# datalogger-v12.net
KiCad netlist of a schematic drawn in EAGLE
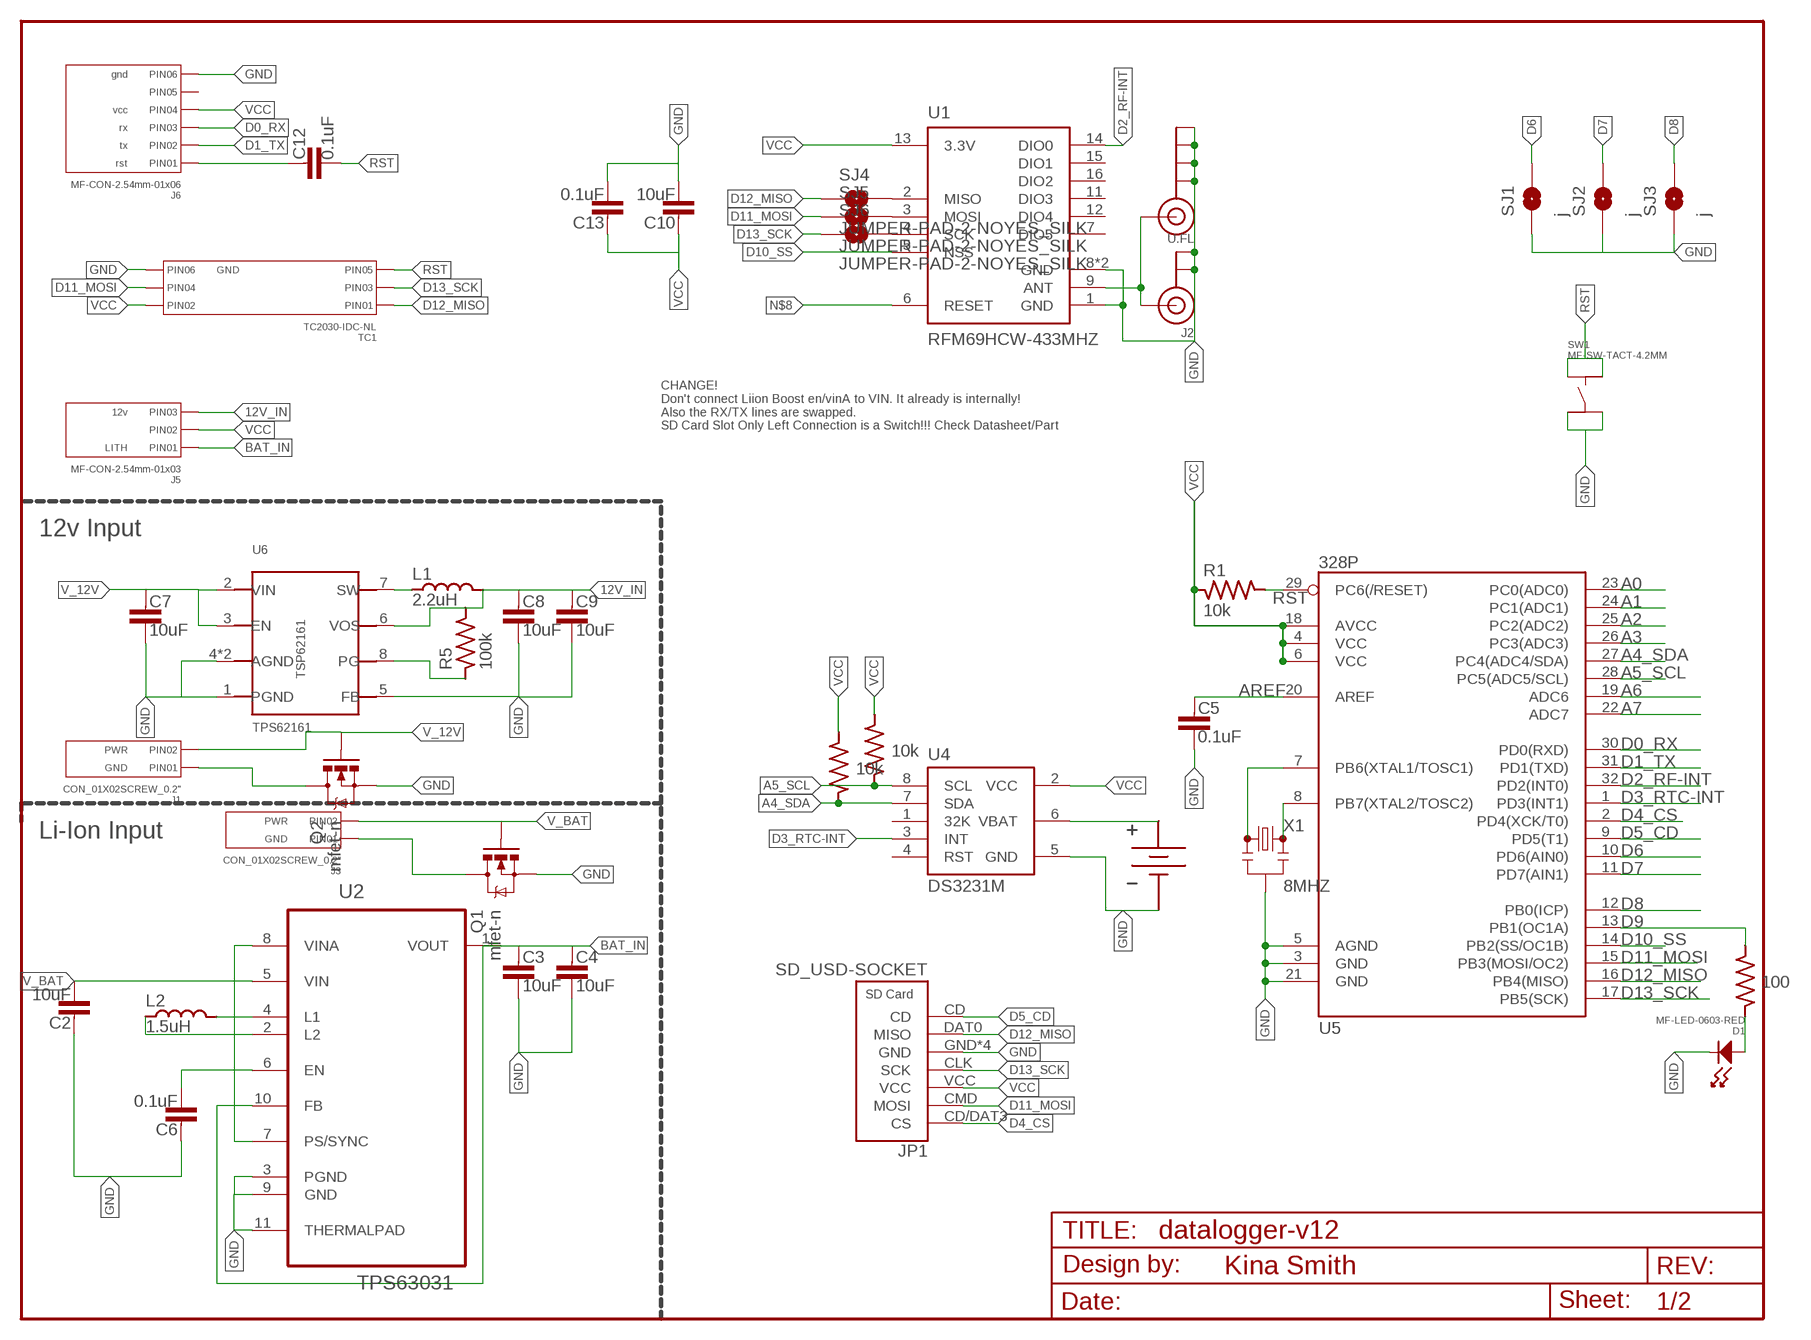
[diagram p0: schematic, sheet 1]
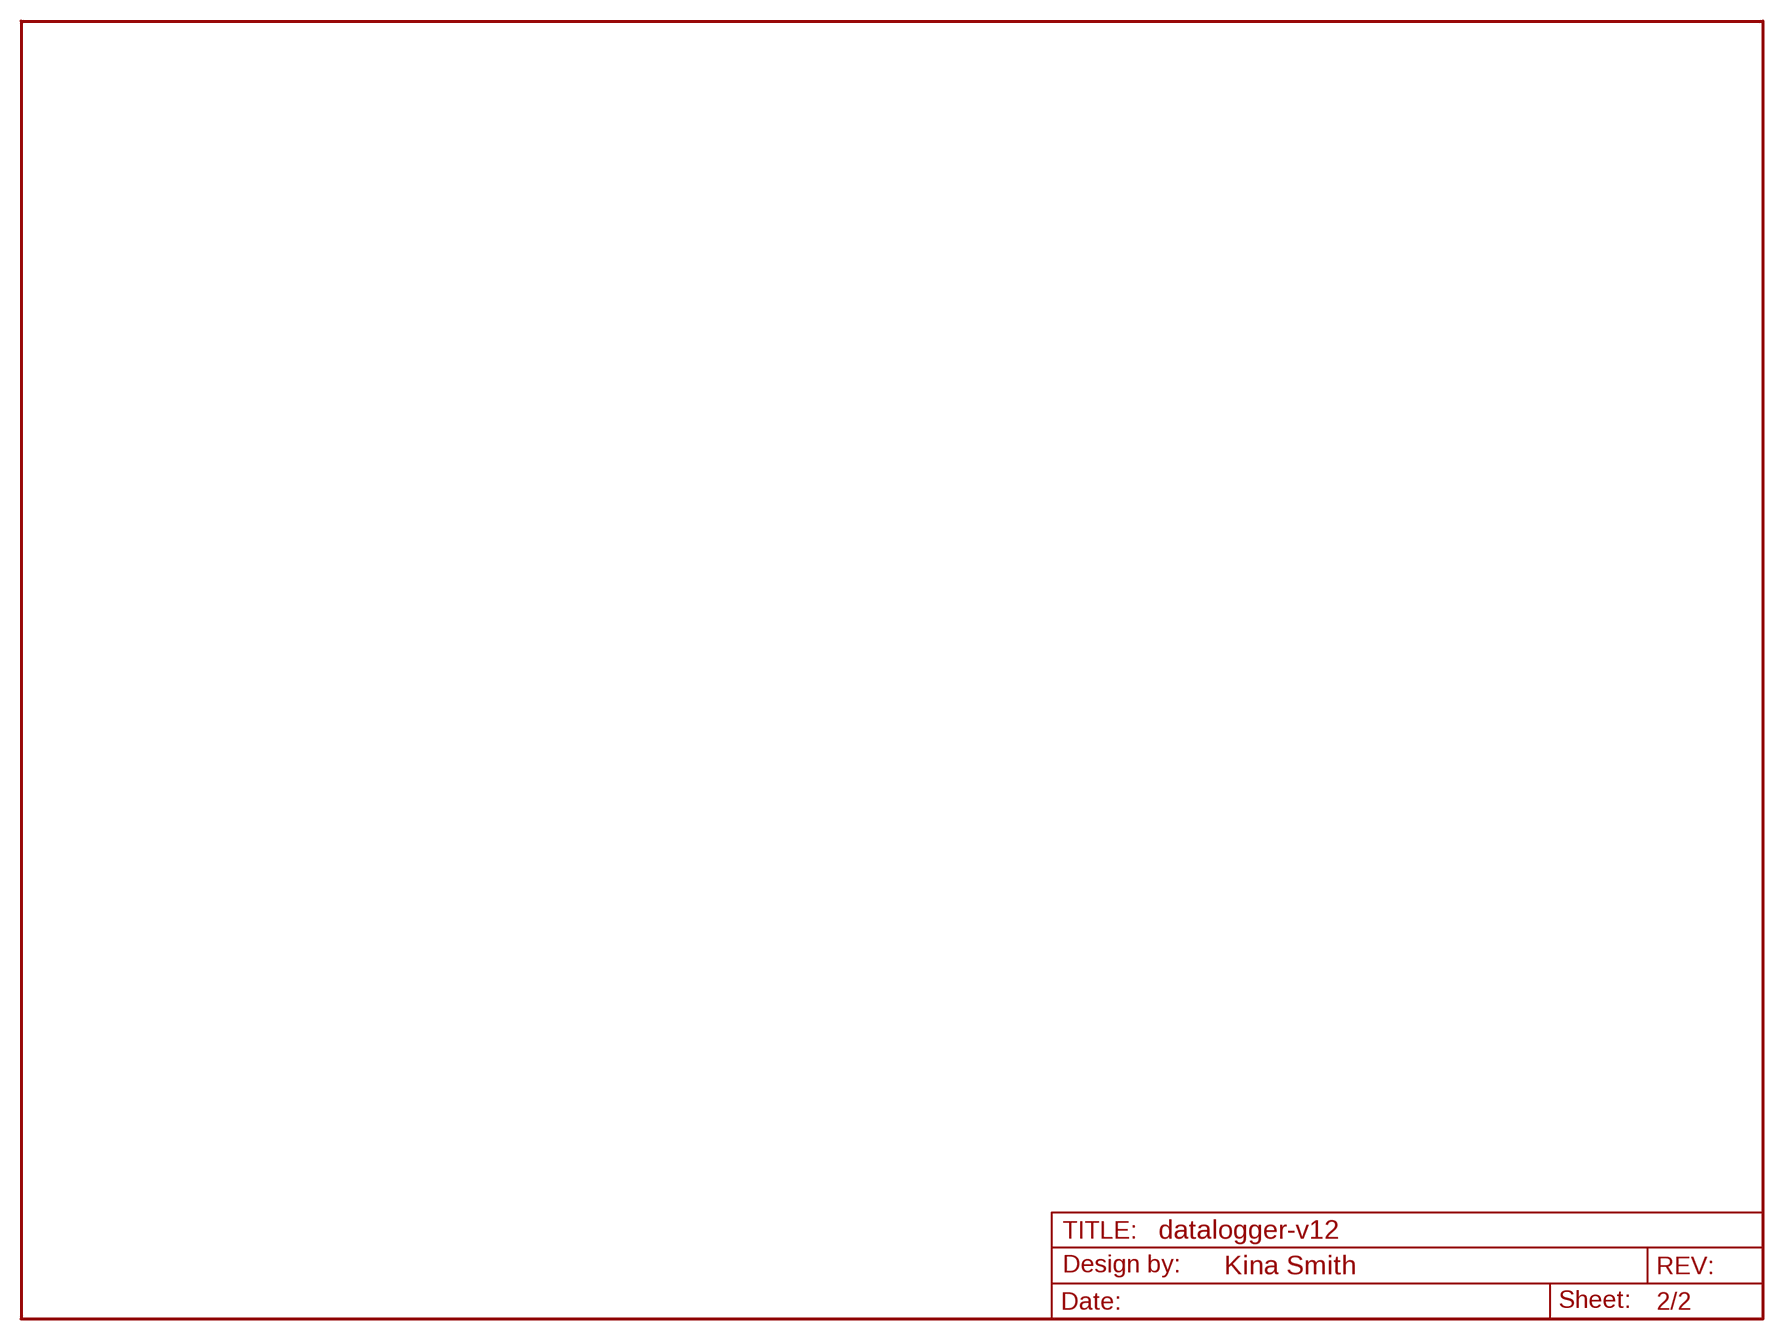
[diagram p1: schematic, sheet 2]

(export (version "E")
  (design (tool "Eeschema 10.0.6"))
  (components
    (comp (ref "BAT1")
      (value "BATTERY_HOLDER12MM")
      (footprint "eagle-import:BAT_12MM")
      (fields (field (name "PARTNO") "BK-885-TR"))
      (libsource (lib "eagle-import") (part "BATTERY_HOLDER12MM"))
    )
    (comp (ref "C2")
      (value "10uF")
      (footprint "eagle-import:C0805-N")
      (fields (field (name "PARTNO") "GRM21BR61C106KE15L"))
      (libsource (lib "eagle-import") (part "CAPACITOR_NP0805-N"))
    )
    (comp (ref "C3")
      (value "10uF")
      (footprint "eagle-import:C0805-N")
      (fields (field (name "PARTNO") "GRM21BR61C106KE15L"))
      (libsource (lib "eagle-import") (part "CAPACITOR_NP0805-N"))
    )
    (comp (ref "C4")
      (value "10uF")
      (footprint "eagle-import:C0805-N")
      (fields (field (name "PARTNO") "GRM21BR61C106KE15L"))
      (libsource (lib "eagle-import") (part "CAPACITOR_NP0805-N"))
    )
    (comp (ref "C5")
      (value "0.1uF")
      (footprint "eagle-import:C0603-N")
      (fields (field (name "PARTNO") "CC0603KRX7R7BB104"))
      (libsource (lib "eagle-import") (part "CAPACITOR_NP0603-N"))
    )
    (comp (ref "C6")
      (value "0.1uF")
      (footprint "eagle-import:C0603-N")
      (fields (field (name "PARTNO") "CC0603KRX7R7BB104"))
      (libsource (lib "eagle-import") (part "CAPACITOR_NP0603-N"))
    )
    (comp (ref "C7")
      (value "10uF")
      (footprint "eagle-import:C0805-N")
      (fields (field (name "PARTNO") "GRM21BR61C106KE15L"))
      (libsource (lib "eagle-import") (part "CAPACITOR_NP0805-N"))
    )
    (comp (ref "C8")
      (value "10uF")
      (footprint "eagle-import:C0805-N")
      (fields (field (name "PARTNO") "GRM21BR61C106KE15L"))
      (libsource (lib "eagle-import") (part "CAPACITOR_NP0805-N"))
    )
    (comp (ref "C9")
      (value "10uF")
      (footprint "eagle-import:C0805-N")
      (fields (field (name "PARTNO") "GRM21BR61C106KE15L"))
      (libsource (lib "eagle-import") (part "CAPACITOR_NP0805-N"))
    )
    (comp (ref "C10")
      (value "10uF")
      (footprint "eagle-import:C0805-N")
      (fields (field (name "PARTNO") "GRM21BR61C106KE15L"))
      (libsource (lib "eagle-import") (part "CAPACITOR_NP0805-N"))
    )
    (comp (ref "C12")
      (value "0.1uF")
      (footprint "eagle-import:C0603-N")
      (fields (field (name "PARTNO") "CC0603KRX7R7BB104"))
      (libsource (lib "eagle-import") (part "CAPACITOR_NP0603-N"))
    )
    (comp (ref "C13")
      (value "0.1uF")
      (footprint "eagle-import:C0603-N")
      (fields (field (name "PARTNO") "CC0603KRX7R7BB104"))
      (libsource (lib "eagle-import") (part "CAPACITOR_NP0603-N"))
    )
    (comp (ref "D1")
      (value "MF-LED-0603-RED")
      (footprint "eagle-import:LED0603")
      (fields (field (name "HOUSEPART") "YES") (field (name "PARTNO") "LTST-C191KRKT"))
      (libsource (lib "eagle-import") (part "LED_SINGLE-0603-RED"))
    )
    (comp (ref "FRAME1")
      (value "FRAME-LETTERNO_PACKAGE")
      (footprint "eagle-import:DUMMY")
      (fields (field (name "DESIGNER") "Nobody"))
      (libsource (lib "eagle-import") (part "FRAME-LETTERNO_PACKAGE"))
    )
    (comp (ref "J1")
      (value "CON_01X02SCREW_0.2\"")
      (footprint "eagle-import:SCREW_TERM_2POS")
      (fields (field (name "PARTNO") "1729128"))
      (libsource (lib "eagle-import") (part "CON_01X02SCREW_0.2{dblquote}"))
    )
    (comp (ref "J2")
      (value "U.FL")
      (footprint "eagle-import:ADAFRUIT_U.FL")
      (fields (field (name "PARTNO") "U.FL-R-SMT-1(10)"))
      (libsource (lib "eagle-import") (part "ANTENNA_U.FL"))
    )
    (comp (ref "J3")
      (value "CON_01X02SCREW_0.2\"")
      (footprint "eagle-import:SCREW_TERM_2POS")
      (fields (field (name "PARTNO") "1729128"))
      (libsource (lib "eagle-import") (part "CON_01X02SCREW_0.2{dblquote}"))
    )
    (comp (ref "J4")
      (value "ANTENNA_SMA_EDGE")
      (footprint "eagle-import:SMA-EDGE")
      (fields (field (name "PARTNO") "EMPCB.SMAFSTJ.B.HT"))
      (libsource (lib "eagle-import") (part "ANTENNA_SMA_EDGE"))
    )
    (comp (ref "J5")
      (value "MF-CON-2.54mm-01x03")
      (footprint "eagle-import:PTH_2.54MM_01X03")
      (fields
        (field (name "HOUSEPART") "YES")
        (field (name "LABEL01") "LITH")
        (field (name "LABEL03") "12v")
        (field (name "PARTNO") "NA")
      )
      (libsource (lib "eagle-import") (part "CON_01X03_PTH_2.54MM"))
    )
    (comp (ref "J6")
      (value "MF-CON-2.54mm-01x06")
      (footprint "eagle-import:PTH_2.54MM_01X06")
      (fields
        (field (name "HOUSEPART") "YES")
        (field (name "LABEL01") "rst")
        (field (name "LABEL02") "tx")
        (field (name "LABEL03") "rx")
        (field (name "LABEL04") "vcc")
        (field (name "LABEL06") "gnd")
        (field (name "PARTNO") "NA")
      )
      (libsource (lib "eagle-import") (part "CON_01X06_PTH_2.54MM"))
    )
    (comp (ref "JP1")
      (value "SD_USD-SOCKET")
      (footprint "eagle-import:MICRO-SD-SOCKET-SDIO")
      (fields (field (name "PARTNO") "101-00660-68-6"))
      (libsource (lib "eagle-import") (part "SD_USD-SOCKET"))
    )
    (comp (ref "L1")
      (value "2.2uH")
      (footprint "eagle-import:L2520")
      (fields (field (name "PARTNO") "VLS252012T-2R2M1R3 "))
      (libsource (lib "eagle-import") (part "INDUCTOR2520"))
    )
    (comp (ref "L2")
      (value "1.5uH")
      (footprint "eagle-import:L3030")
      (fields (field (name "PARTNO") "NR3015T1R5N"))
      (libsource (lib "eagle-import") (part "INDUCTOR3030"))
    )
    (comp (ref "Q1")
      (value "mfet-n")
      (footprint "eagle-import:SOT23-3")
      (fields (field (name "PARTNO") "SI2312BDS-T1-GE3"))
      (libsource (lib "eagle-import") (part "MOSFET-NCHANNELSOT23-3"))
    )
    (comp (ref "Q2")
      (value "mfet-n")
      (footprint "eagle-import:SOT23-3")
      (fields (field (name "PARTNO") "SI2312BDS-T1-GE3"))
      (libsource (lib "eagle-import") (part "MOSFET-NCHANNELSOT23-3"))
    )
    (comp (ref "R1")
      (value "10k")
      (footprint "eagle-import:R0603-N")
      (fields (field (name "PARTNO") "RC0603FR-0710KL"))
      (libsource (lib "eagle-import") (part "RESISTOR0603-N"))
    )
    (comp (ref "R2")
      (value "100")
      (footprint "eagle-import:R0603-N")
      (fields (field (name "PARTNO") "RC0603FR-07100RL"))
      (libsource (lib "eagle-import") (part "RESISTOR0603-N"))
    )
    (comp (ref "R3")
      (value "10k")
      (footprint "eagle-import:R0603-N")
      (fields (field (name "PARTNO") "RC0603FR-0710KL"))
      (libsource (lib "eagle-import") (part "RESISTOR0603-N"))
    )
    (comp (ref "R4")
      (value "10k")
      (footprint "eagle-import:R0603-N")
      (fields (field (name "PARTNO") "RC0603FR-0710KL"))
      (libsource (lib "eagle-import") (part "RESISTOR0603-N"))
    )
    (comp (ref "R5")
      (value "100k")
      (footprint "eagle-import:R0603-N")
      (fields (field (name "PARTNO") "RC0603FR-07100KL"))
      (libsource (lib "eagle-import") (part "RESISTOR0603-N"))
    )
    (comp (ref "SJ1")
      (value "j")
      (footprint "eagle-import:PAD-JUMPER-2-NO_YES_SILK")
      (fields (field (name "PARTNO") "NA"))
      (libsource (lib "eagle-import") (part "JUMPER-PAD-2-NOYES_SILK"))
    )
    (comp (ref "SJ2")
      (value "j")
      (footprint "eagle-import:PAD-JUMPER-2-NO_YES_SILK")
      (fields (field (name "PARTNO") "NA"))
      (libsource (lib "eagle-import") (part "JUMPER-PAD-2-NOYES_SILK"))
    )
    (comp (ref "SJ3")
      (value "j")
      (footprint "eagle-import:PAD-JUMPER-2-NO_YES_SILK")
      (fields (field (name "PARTNO") "NA"))
      (libsource (lib "eagle-import") (part "JUMPER-PAD-2-NOYES_SILK"))
    )
    (comp (ref "SJ4")
      (value "JUMPER-PAD-2-NOYES_SILK")
      (footprint "eagle-import:PAD-JUMPER-2-NO_YES_SILK")
      (fields (field (name "PARTNO") "NA"))
      (libsource (lib "eagle-import") (part "JUMPER-PAD-2-NOYES_SILK"))
    )
    (comp (ref "SJ5")
      (value "JUMPER-PAD-2-NOYES_SILK")
      (footprint "eagle-import:PAD-JUMPER-2-NO_YES_SILK")
      (fields (field (name "PARTNO") "NA"))
      (libsource (lib "eagle-import") (part "JUMPER-PAD-2-NOYES_SILK"))
    )
    (comp (ref "SJ6")
      (value "JUMPER-PAD-2-NOYES_SILK")
      (footprint "eagle-import:PAD-JUMPER-2-NO_YES_SILK")
      (fields (field (name "PARTNO") "NA"))
      (libsource (lib "eagle-import") (part "JUMPER-PAD-2-NOYES_SILK"))
    )
    (comp (ref "SW1")
      (value "MF-SW-TACT-4.2MM")
      (footprint "eagle-import:TACT4.2MM")
      (fields (field (name "HOUSEPART") "YES") (field (name "PARTNO") "PTS810 SJM 250 SMTR LFS"))
      (libsource (lib "eagle-import") (part "TACT_4.2MM"))
    )
    (comp (ref "TC1")
      (value "TC2030-IDC-NL")
      (footprint "eagle-import:TC2030-IDC-NL")
      (fields (field (name "HOUSEPART") "NO") (field (name "PARTNO") "NA"))
      (libsource (lib "eagle-import") (part "CON_02X03_TC2030-IDC-NL_AVRISP"))
    )
    (comp (ref "U1")
      (value "RFM69HCW-433MHZ")
      (footprint "eagle-import:RFM69HCW-XXXS2")
      (fields (field (name "PARTNO") "COM-13910"))
      (libsource (lib "eagle-import") (part "RFM69HCW-433MHZ"))
    )
    (comp (ref "U2")
      (value "TPS63031")
      (footprint "eagle-import:SON50P260X260X80-11N")
      (fields (field (name "MPN") "TPS63031DSK") (field (name "PARTNO") "TPS63031DSKR"))
      (libsource (lib "eagle-import") (part "TPS63031"))
    )
    (comp (ref "U4")
      (value "DS3231M")
      (footprint "eagle-import:SO08")
      (fields (field (name "PARTNO") "DS3231MZ/V+"))
      (libsource (lib "eagle-import") (part "DS3231M"))
    )
    (comp (ref "U5")
      (value "328P")
      (footprint "eagle-import:TQFP32-08")
      (fields (field (name "PARTNO") "ATMEGA328P-AU"))
      (libsource (lib "eagle-import") (part "ATMEGA328P-AU"))
    )
    (comp (ref "U6")
      (value "TPS62161")
      (footprint "eagle-import:WSON-8")
      (fields (field (name "PARTNO") "TPS62161DSGR"))
      (libsource (lib "eagle-import") (part "TPS62161"))
    )
    (comp (ref "X1")
      (value "8MHZ")
      (footprint "eagle-import:RESONATOR-SMD")
      (fields (field (name "PARTNO") "CSTCE8M00G55-R0"))
      (libsource (lib "eagle-import") (part "RESONATOR8MHZ"))
    )
    (comp (ref "FRAME3")
      (value "FRAME-LETTERNO_PACKAGE")
      (footprint "eagle-import:DUMMY")
      (fields (field (name "DESIGNER") "Nobody"))
      (libsource (lib "eagle-import") (part "FRAME-LETTERNO_PACKAGE"))
    )
  )
  (nets
    (net (code "1") (name "12V_IN") (class "Default")
      (node (ref "C8") (pin "1") (pinfunction "1_1") (pintype "passive"))
      (node (ref "C9") (pin "1") (pinfunction "1_1") (pintype "passive"))
      (node (ref "J5") (pin "P$3") (pinfunction "PIN3_P$3") (pintype "bidirectional"))
      (node (ref "L1") (pin "P$2") (pinfunction "P$2_P$2") (pintype "passive"))
      (node (ref "R5") (pin "2") (pinfunction "P$2_2") (pintype "passive"))
      (node (ref "U6") (pin "6") (pinfunction "VOS_6") (pintype "bidirectional"))
    )
    (net (code "2") (name "A0") (class "Default")
      (node (ref "U5") (pin "23") (pinfunction "PC0(ADC0)_23") (pintype "bidirectional"))
    )
    (net (code "3") (name "A1") (class "Default")
      (node (ref "U5") (pin "24") (pinfunction "PC1(ADC1)_24") (pintype "bidirectional"))
    )
    (net (code "4") (name "A2") (class "Default")
      (node (ref "U5") (pin "25") (pinfunction "PC2(ADC2)_25") (pintype "bidirectional"))
    )
    (net (code "5") (name "A3") (class "Default")
      (node (ref "U5") (pin "26") (pinfunction "PC3(ADC3)_26") (pintype "bidirectional"))
    )
    (net (code "6") (name "A4_SDA") (class "Default")
      (node (ref "R4") (pin "1") (pinfunction "P$1_1") (pintype "passive"))
      (node (ref "U4") (pin "7") (pinfunction "SDA_7") (pintype "bidirectional"))
      (node (ref "U5") (pin "27") (pinfunction "PC4(ADC4/SDA)_27") (pintype "bidirectional"))
    )
    (net (code "7") (name "A5_SCL") (class "Default")
      (node (ref "R3") (pin "1") (pinfunction "P$1_1") (pintype "passive"))
      (node (ref "U4") (pin "8") (pinfunction "SCL_8") (pintype "bidirectional"))
      (node (ref "U5") (pin "28") (pinfunction "PC5(ADC5/SCL)_28") (pintype "bidirectional"))
    )
    (net (code "8") (name "A6") (class "Default")
      (node (ref "U5") (pin "19") (pinfunction "ADC6_19") (pintype "bidirectional"))
    )
    (net (code "9") (name "A7") (class "Default")
      (node (ref "U5") (pin "22") (pinfunction "ADC7_22") (pintype "bidirectional"))
    )
    (net (code "10") (name "AREF") (class "Default")
      (node (ref "C5") (pin "1") (pinfunction "1_1") (pintype "passive"))
      (node (ref "U5") (pin "20") (pinfunction "AREF_20") (pintype "bidirectional"))
    )
    (net (code "11") (name "BAT_IN") (class "Default")
      (node (ref "C3") (pin "1") (pinfunction "1_1") (pintype "passive"))
      (node (ref "C4") (pin "1") (pinfunction "1_1") (pintype "passive"))
      (node (ref "J5") (pin "P$1") (pinfunction "PIN1_P$1") (pintype "bidirectional"))
      (node (ref "U2") (pin "1") (pinfunction "VOUT_1") (pintype "output"))
      (node (ref "U2") (pin "10") (pinfunction "FB_10") (pintype "input"))
    )
    (net (code "12") (name "D0_RX") (class "Default")
      (node (ref "J6") (pin "P$3") (pinfunction "PIN3_P$3") (pintype "bidirectional"))
      (node (ref "U5") (pin "30") (pinfunction "PD0(RXD)_30") (pintype "bidirectional"))
    )
    (net (code "13") (name "D1_TX") (class "Default")
      (node (ref "J6") (pin "P$2") (pinfunction "PIN2_P$2") (pintype "bidirectional"))
      (node (ref "U5") (pin "31") (pinfunction "PD1(TXD)_31") (pintype "bidirectional"))
    )
    (net (code "14") (name "D2_RF-INT") (class "Default")
      (node (ref "U1") (pin "14") (pinfunction "DIO0_14") (pintype "bidirectional"))
      (node (ref "U5") (pin "32") (pinfunction "PD2(INT0)_32") (pintype "bidirectional"))
    )
    (net (code "15") (name "D3_RTC-INT") (class "Default")
      (node (ref "U4") (pin "3") (pinfunction "INT_3") (pintype "bidirectional"))
      (node (ref "U5") (pin "1") (pinfunction "PD3(INT1)_1") (pintype "bidirectional"))
    )
    (net (code "16") (name "D4_CS") (class "Default")
      (node (ref "JP1") (pin "CD/DAT3") (pinfunction "CS_CD/DAT3") (pintype "bidirectional"))
      (node (ref "U5") (pin "2") (pinfunction "PD4(XCK/T0)_2") (pintype "bidirectional"))
    )
    (net (code "17") (name "D5_CD") (class "Default")
      (node (ref "JP1") (pin "CD") (pinfunction "CD_CD") (pintype "bidirectional"))
      (node (ref "U5") (pin "9") (pinfunction "PD5(T1)_9") (pintype "bidirectional"))
    )
    (net (code "18") (name "D6") (class "Default")
      (node (ref "SJ1") (pin "2") (pinfunction "2_2") (pintype "passive"))
      (node (ref "U5") (pin "10") (pinfunction "PD6(AIN0)_10") (pintype "bidirectional"))
    )
    (net (code "19") (name "D7") (class "Default")
      (node (ref "SJ2") (pin "2") (pinfunction "2_2") (pintype "passive"))
      (node (ref "U5") (pin "11") (pinfunction "PD7(AIN1)_11") (pintype "bidirectional"))
    )
    (net (code "20") (name "D8") (class "Default")
      (node (ref "SJ3") (pin "2") (pinfunction "2_2") (pintype "passive"))
      (node (ref "U5") (pin "12") (pinfunction "PB0(ICP)_12") (pintype "bidirectional"))
    )
    (net (code "21") (name "D9") (class "Default")
      (node (ref "R2") (pin "2") (pinfunction "P$2_2") (pintype "passive"))
      (node (ref "U5") (pin "13") (pinfunction "PB1(OC1A)_13") (pintype "bidirectional"))
    )
    (net (code "22") (name "D10_SS") (class "Default")
      (node (ref "U1") (pin "5") (pinfunction "NSS_5") (pintype "input"))
      (node (ref "U5") (pin "14") (pinfunction "PB2(SS/OC1B)_14") (pintype "bidirectional"))
    )
    (net (code "23") (name "D11_MOSI") (class "Default")
      (node (ref "JP1") (pin "CMD") (pinfunction "MOSI_CMD") (pintype "bidirectional"))
      (node (ref "SJ5") (pin "1") (pinfunction "1_1") (pintype "passive"))
      (node (ref "TC1") (pin "P$4") (pinfunction "PIN4_P$4") (pintype "bidirectional"))
      (node (ref "U5") (pin "15") (pinfunction "PB3(MOSI/OC2)_15") (pintype "bidirectional"))
    )
    (net (code "24") (name "D12_MISO") (class "Default")
      (node (ref "JP1") (pin "DAT0") (pinfunction "MISO_DAT0") (pintype "bidirectional"))
      (node (ref "SJ4") (pin "1") (pinfunction "1_1") (pintype "passive"))
      (node (ref "TC1") (pin "P$1") (pinfunction "PIN1_P$1") (pintype "bidirectional"))
      (node (ref "U5") (pin "16") (pinfunction "PB4(MISO)_16") (pintype "bidirectional"))
    )
    (net (code "25") (name "D13_SCK") (class "Default")
      (node (ref "JP1") (pin "CLK") (pinfunction "SCK_CLK") (pintype "bidirectional"))
      (node (ref "SJ6") (pin "1") (pinfunction "1_1") (pintype "passive"))
      (node (ref "TC1") (pin "P$3") (pinfunction "PIN3_P$3") (pintype "bidirectional"))
      (node (ref "U5") (pin "17") (pinfunction "PB5(SCK)_17") (pintype "bidirectional"))
    )
    (net (code "26") (name "GND") (class "Default")
      (node (ref "BAT1") (pin "GND") (pinfunction "GND_GND") (pintype "bidirectional"))
      (node (ref "C10") (pin "2") (pinfunction "2_2") (pintype "passive"))
      (node (ref "C13") (pin "2") (pinfunction "2_2") (pintype "passive"))
      (node (ref "C2") (pin "1") (pinfunction "1_1") (pintype "passive"))
      (node (ref "C3") (pin "2") (pinfunction "2_2") (pintype "passive"))
      (node (ref "C4") (pin "2") (pinfunction "2_2") (pintype "passive"))
      (node (ref "C5") (pin "2") (pinfunction "2_2") (pintype "passive"))
      (node (ref "C6") (pin "1") (pinfunction "1_1") (pintype "passive"))
      (node (ref "C7") (pin "2") (pinfunction "2_2") (pintype "passive"))
      (node (ref "C8") (pin "2") (pinfunction "2_2") (pintype "passive"))
      (node (ref "C9") (pin "2") (pinfunction "2_2") (pintype "passive"))
      (node (ref "D1") (pin "CATHODE") (pinfunction "CATHODE_CATHODE") (pintype "power_in"))
      (node (ref "J2") (pin "1") (pinfunction "GND_1") (pintype "passive"))
      (node (ref "J2") (pin "2") (pinfunction "GND_2") (pintype "passive"))
      (node (ref "J4") (pin "GND@0") (pinfunction "GND_GND@0") (pintype "bidirectional"))
      (node (ref "J4") (pin "GND@1") (pinfunction "GND_GND@1") (pintype "bidirectional"))
      (node (ref "J4") (pin "GND@2") (pinfunction "GND_GND@2") (pintype "bidirectional"))
      (node (ref "J4") (pin "GND@3") (pinfunction "GND_GND@3") (pintype "bidirectional"))
      (node (ref "J6") (pin "P$6") (pinfunction "PIN6_P$6") (pintype "bidirectional"))
      (node (ref "JP1") (pin "GND") (pinfunction "GND_GND") (pintype "bidirectional"))
      (node (ref "JP1") (pin "GND1") (pinfunction "GND_GND1") (pintype "bidirectional"))
      (node (ref "JP1") (pin "GND2") (pinfunction "GND_GND2") (pintype "bidirectional"))
      (node (ref "JP1") (pin "GND3") (pinfunction "GND_GND3") (pintype "bidirectional"))
      (node (ref "Q1") (pin "2") (pinfunction "S_2") (pintype "passive"))
      (node (ref "Q2") (pin "2") (pinfunction "S_2") (pintype "passive"))
      (node (ref "SJ1") (pin "1") (pinfunction "1_1") (pintype "passive"))
      (node (ref "SJ2") (pin "1") (pinfunction "1_1") (pintype "passive"))
      (node (ref "SJ3") (pin "1") (pinfunction "1_1") (pintype "passive"))
      (node (ref "SW1") (pin "P$3") (pinfunction "P$3_P$3") (pintype "bidirectional"))
      (node (ref "SW1") (pin "P$4") (pinfunction "P$4_P$4") (pintype "bidirectional"))
      (node (ref "TC1") (pin "P$6") (pinfunction "PIN6_P$6") (pintype "bidirectional"))
      (node (ref "U1") (pin "1") (pinfunction "GND_1") (pintype "power_in"))
      (node (ref "U1") (pin "10") (pinfunction "GND_10") (pintype "power_in"))
      (node (ref "U1") (pin "8") (pinfunction "GND_8") (pintype "power_in"))
      (node (ref "U2") (pin "11") (pinfunction "THERMALPAD_11") (pintype "passive"))
      (node (ref "U2") (pin "3") (pinfunction "PGND_3") (pintype "passive"))
      (node (ref "U2") (pin "9") (pinfunction "GND_9") (pintype "passive"))
      (node (ref "U4") (pin "5") (pinfunction "GND_5") (pintype "power_in"))
      (node (ref "U5") (pin "21") (pinfunction "GND_21") (pintype "bidirectional"))
      (node (ref "U5") (pin "3") (pinfunction "GND_3") (pintype "bidirectional"))
      (node (ref "U5") (pin "5") (pinfunction "AGND_5") (pintype "bidirectional"))
      (node (ref "U6") (pin "1") (pinfunction "PGND_1") (pintype "bidirectional"))
      (node (ref "U6") (pin "4") (pinfunction "AGND_4") (pintype "bidirectional"))
      (node (ref "U6") (pin "5") (pinfunction "FB_5") (pintype "bidirectional"))
      (node (ref "U6") (pin "P$9") (pinfunction "AGND_P$9") (pintype "bidirectional"))
      (node (ref "X1") (pin "2") (pinfunction "2_2") (pintype "passive"))
    )
    (net (code "27") (name "N$8") (class "Default")
      (node (ref "U1") (pin "6") (pinfunction "RESET_6") (pintype "input"))
    )
    (net (code "28") (name "Net-(J1-PIN1)") (class "Default")
      (node (ref "J1") (pin "GND") (pinfunction "PIN1_GND") (pintype "bidirectional"))
      (node (ref "Q2") (pin "3") (pinfunction "D_3") (pintype "passive"))
    )
    (net (code "29") (name "Net-(J2-SIGNAL)") (class "Default")
      (node (ref "J2") (pin "3") (pinfunction "SIGNAL_3") (pintype "passive"))
      (node (ref "J4") (pin "SIG") (pinfunction "SIGNAL_SIG") (pintype "bidirectional"))
      (node (ref "U1") (pin "9") (pinfunction "ANT_9") (pintype "passive"))
    )
    (net (code "30") (name "Net-(J3-PIN1)") (class "Default")
      (node (ref "J3") (pin "GND") (pinfunction "PIN1_GND") (pintype "bidirectional"))
      (node (ref "Q1") (pin "3") (pinfunction "D_3") (pintype "passive"))
    )
    (net (code "31") (name "Net-(J6-PIN1)") (class "Default")
      (node (ref "C12") (pin "1") (pinfunction "1_1") (pintype "passive"))
      (node (ref "J6") (pin "P$1") (pinfunction "PIN1_P$1") (pintype "bidirectional"))
    )
    (net (code "32") (name "Net-(R2-P$1)") (class "Default")
      (node (ref "D1") (pin "ANODE") (pinfunction "ANODE_ANODE") (pintype "power_in"))
      (node (ref "R2") (pin "1") (pinfunction "P$1_1") (pintype "passive"))
    )
    (net (code "33") (name "Net-(R5-P$1)") (class "Default")
      (node (ref "R5") (pin "1") (pinfunction "P$1_1") (pintype "passive"))
      (node (ref "U6") (pin "8") (pinfunction "PG_8") (pintype "bidirectional"))
    )
    (net (code "34") (name "Net-(U1-MISO)") (class "Default")
      (node (ref "SJ4") (pin "2") (pinfunction "2_2") (pintype "passive"))
      (node (ref "U1") (pin "2") (pinfunction "MISO_2") (pintype "bidirectional"))
    )
    (net (code "35") (name "Net-(U1-MOSI)") (class "Default")
      (node (ref "SJ5") (pin "2") (pinfunction "2_2") (pintype "passive"))
      (node (ref "U1") (pin "3") (pinfunction "MOSI_3") (pintype "input"))
    )
    (net (code "36") (name "Net-(U1-SCK)") (class "Default")
      (node (ref "SJ6") (pin "2") (pinfunction "2_2") (pintype "passive"))
      (node (ref "U1") (pin "4") (pinfunction "SCK_4") (pintype "input"))
    )
    (net (code "37") (name "Net-(U2-EN)") (class "Default")
      (node (ref "C6") (pin "2") (pinfunction "2_2") (pintype "passive"))
      (node (ref "U2") (pin "6") (pinfunction "EN_6") (pintype "input"))
      (node (ref "U2") (pin "7") (pinfunction "PS/SYNC_7") (pintype "input"))
      (node (ref "U2") (pin "8") (pinfunction "VINA_8") (pintype "input"))
    )
    (net (code "38") (name "Net-(U2-L1)") (class "Default")
      (node (ref "L2") (pin "P$2") (pinfunction "P$2_P$2") (pintype "passive"))
      (node (ref "U2") (pin "4") (pinfunction "L1_4") (pintype "input"))
    )
    (net (code "39") (name "Net-(U2-L2)") (class "Default")
      (node (ref "L2") (pin "P$1") (pinfunction "P$1_P$1") (pintype "passive"))
      (node (ref "U2") (pin "2") (pinfunction "L2_2") (pintype "input"))
    )
    (net (code "40") (name "Net-(U4-VBAT)") (class "Default")
      (node (ref "BAT1") (pin "PWR@1") (pinfunction "VBAT_PWR@1") (pintype "bidirectional"))
      (node (ref "BAT1") (pin "PWR@2") (pinfunction "VBAT_PWR@2") (pintype "bidirectional"))
      (node (ref "U4") (pin "6") (pinfunction "VBAT_6") (pintype "power_in"))
    )
    (net (code "41") (name "Net-(U5-PB6(XTAL1{slash}TOSC1))") (class "Default")
      (node (ref "U5") (pin "7") (pinfunction "PB6(XTAL1/TOSC1)_7") (pintype "bidirectional"))
      (node (ref "X1") (pin "1") (pinfunction "1_1") (pintype "passive"))
    )
    (net (code "42") (name "Net-(U5-PB7(XTAL2{slash}TOSC2))") (class "Default")
      (node (ref "U5") (pin "8") (pinfunction "PB7(XTAL2/TOSC2)_8") (pintype "bidirectional"))
      (node (ref "X1") (pin "3") (pinfunction "3_3") (pintype "passive"))
    )
    (net (code "43") (name "Net-(U6-SW)") (class "Default")
      (node (ref "L1") (pin "P$1") (pinfunction "P$1_P$1") (pintype "passive"))
      (node (ref "U6") (pin "7") (pinfunction "SW_7") (pintype "bidirectional"))
    )
    (net (code "44") (name "RST") (class "Default")
      (node (ref "C12") (pin "2") (pinfunction "2_2") (pintype "passive"))
      (node (ref "R1") (pin "2") (pinfunction "P$2_2") (pintype "passive"))
      (node (ref "SW1") (pin "P$1") (pinfunction "P$1_P$1") (pintype "bidirectional"))
      (node (ref "SW1") (pin "P$2") (pinfunction "P$2_P$2") (pintype "bidirectional"))
      (node (ref "TC1") (pin "P$5") (pinfunction "PIN5_P$5") (pintype "bidirectional"))
      (node (ref "U5") (pin "29") (pinfunction "PC6(/RESET)_29") (pintype "bidirectional"))
    )
    (net (code "45") (name "VCC") (class "Default")
      (node (ref "C10") (pin "1") (pinfunction "1_1") (pintype "passive"))
      (node (ref "C13") (pin "1") (pinfunction "1_1") (pintype "passive"))
      (node (ref "J5") (pin "P$2") (pinfunction "PIN2_P$2") (pintype "bidirectional"))
      (node (ref "J6") (pin "P$4") (pinfunction "PIN4_P$4") (pintype "bidirectional"))
      (node (ref "JP1") (pin "VCC") (pinfunction "VCC_VCC") (pintype "bidirectional"))
      (node (ref "R1") (pin "1") (pinfunction "P$1_1") (pintype "passive"))
      (node (ref "R3") (pin "2") (pinfunction "P$2_2") (pintype "passive"))
      (node (ref "R4") (pin "2") (pinfunction "P$2_2") (pintype "passive"))
      (node (ref "TC1") (pin "P$2") (pinfunction "PIN2_P$2") (pintype "bidirectional"))
      (node (ref "U1") (pin "13") (pinfunction "3.3V_13") (pintype "power_in"))
      (node (ref "U4") (pin "2") (pinfunction "VCC_2") (pintype "power_in"))
      (node (ref "U5") (pin "18") (pinfunction "AVCC_18") (pintype "bidirectional"))
      (node (ref "U5") (pin "4") (pinfunction "VCC_4") (pintype "bidirectional"))
      (node (ref "U5") (pin "6") (pinfunction "VCC_6") (pintype "bidirectional"))
    )
    (net (code "46") (name "V_12V") (class "Default")
      (node (ref "C7") (pin "1") (pinfunction "1_1") (pintype "passive"))
      (node (ref "J1") (pin "PWR") (pinfunction "PIN2_PWR") (pintype "bidirectional"))
      (node (ref "Q2") (pin "1") (pinfunction "G_1") (pintype "passive"))
      (node (ref "U6") (pin "2") (pinfunction "VIN_2") (pintype "bidirectional"))
      (node (ref "U6") (pin "3") (pinfunction "EN_3") (pintype "bidirectional"))
    )
    (net (code "47") (name "V_BAT") (class "Default")
      (node (ref "C2") (pin "2") (pinfunction "2_2") (pintype "passive"))
      (node (ref "J3") (pin "PWR") (pinfunction "PIN2_PWR") (pintype "bidirectional"))
      (node (ref "Q1") (pin "1") (pinfunction "G_1") (pintype "passive"))
      (node (ref "U2") (pin "5") (pinfunction "VIN_5") (pintype "input"))
    )
    (net (code "48") (name "unconnected-(J6-PIN5-PadP$5)") (class "Default")
      (node (ref "J6") (pin "P$5") (pinfunction "PIN5_P$5") (pintype "bidirectional"))
    )
    (net (code "49") (name "unconnected-(U1-DIO1-Pad15)") (class "Default")
      (node (ref "U1") (pin "15") (pinfunction "DIO1_15") (pintype "bidirectional"))
    )
    (net (code "50") (name "unconnected-(U1-DIO2-Pad16)") (class "Default")
      (node (ref "U1") (pin "16") (pinfunction "DIO2_16") (pintype "bidirectional"))
    )
    (net (code "51") (name "unconnected-(U1-DIO3-Pad11)") (class "Default")
      (node (ref "U1") (pin "11") (pinfunction "DIO3_11") (pintype "bidirectional"))
    )
    (net (code "52") (name "unconnected-(U1-DIO4-Pad12)") (class "Default")
      (node (ref "U1") (pin "12") (pinfunction "DIO4_12") (pintype "bidirectional"))
    )
    (net (code "53") (name "unconnected-(U1-DIO5-Pad7)") (class "Default")
      (node (ref "U1") (pin "7") (pinfunction "DIO5_7") (pintype "bidirectional"))
    )
    (net (code "54") (name "unconnected-(U4-32K-Pad1)") (class "Default")
      (node (ref "U4") (pin "1") (pinfunction "32K_1") (pintype "bidirectional"))
    )
    (net (code "55") (name "unconnected-(U4-RST-Pad4)") (class "Default")
      (node (ref "U4") (pin "4") (pinfunction "RST_4") (pintype "bidirectional"))
    )
  )
)
